# variator_380V_v2_0.net
KiCad netlist of a schematic drawn in EAGLE
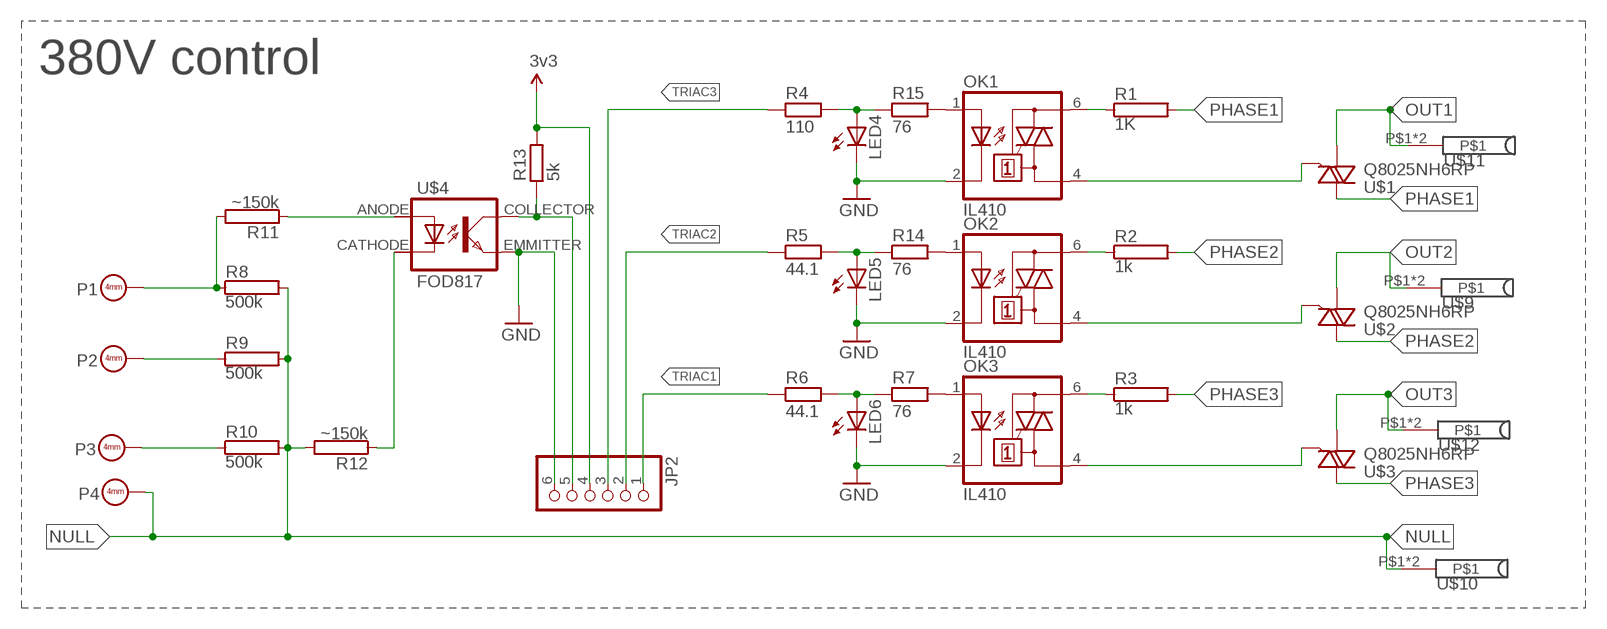
[diagram p0: schematic, sheet 1]

(export (version "E")
  (design (tool "Eeschema 10.0.6"))
  (components
    (comp (ref "JP2")
      (value "PINHD-1X6/90")
      (footprint "eagle-import:1X06_90")
      (libsource (lib "eagle-import") (part "PINHD-1X6/90"))
    )
    (comp (ref "LED4")
      (value "LED5MM")
      (footprint "eagle-import:LED5MM")
      (libsource (lib "eagle-import") (part "LED5MM"))
    )
    (comp (ref "LED5")
      (value "LED5MM")
      (footprint "eagle-import:LED5MM")
      (libsource (lib "eagle-import") (part "LED5MM"))
    )
    (comp (ref "LED6")
      (value "LED5MM")
      (footprint "eagle-import:LED5MM")
      (libsource (lib "eagle-import") (part "LED5MM"))
    )
    (comp (ref "OK1")
      (value "IL410")
      (footprint "eagle-import:DIL06")
      (fields (field (name "MF") "VISHAY/TELEFUNKEN"))
      (libsource (lib "eagle-import") (part "IL410"))
    )
    (comp (ref "OK2")
      (value "IL410")
      (footprint "eagle-import:DIL06")
      (fields (field (name "MF") "VISHAY/TELEFUNKEN"))
      (libsource (lib "eagle-import") (part "IL410"))
    )
    (comp (ref "OK3")
      (value "IL410")
      (footprint "eagle-import:DIL06")
      (fields (field (name "MF") "VISHAY/TELEFUNKEN"))
      (libsource (lib "eagle-import") (part "IL410"))
    )
    (comp (ref "P1")
      (value "BANANA")
      (footprint "eagle-import:BANANA")
      (libsource (lib "eagle-import") (part "adi_v1.4_BANANA"))
    )
    (comp (ref "P2")
      (value "BANANA")
      (footprint "eagle-import:BANANA")
      (libsource (lib "eagle-import") (part "adi_v1.4_BANANA"))
    )
    (comp (ref "P3")
      (value "BANANA")
      (footprint "eagle-import:BANANA")
      (libsource (lib "eagle-import") (part "adi_v1.4_BANANA"))
    )
    (comp (ref "P4")
      (value "BANANA")
      (footprint "eagle-import:BANANA")
      (libsource (lib "eagle-import") (part "adi_v1.4_BANANA"))
    )
    (comp (ref "R1")
      (value "1K")
      (footprint "eagle-import:HPS58")
      (libsource (lib "eagle-import") (part "RHPS58"))
    )
    (comp (ref "R2")
      (value "1k")
      (footprint "eagle-import:HPS58")
      (libsource (lib "eagle-import") (part "RHPS58"))
    )
    (comp (ref "R3")
      (value "1k")
      (footprint "eagle-import:HPS58")
      (libsource (lib "eagle-import") (part "RHPS58"))
    )
    (comp (ref "R4")
      (value "110")
      (footprint "eagle-import:1206")
      (libsource (lib "eagle-import") (part "R1206"))
    )
    (comp (ref "R5")
      (value "44.1")
      (footprint "eagle-import:1206")
      (libsource (lib "eagle-import") (part "R1206"))
    )
    (comp (ref "R6")
      (value "44.1")
      (footprint "eagle-import:1206")
      (libsource (lib "eagle-import") (part "R1206"))
    )
    (comp (ref "R7")
      (value "76")
      (footprint "eagle-import:1206")
      (libsource (lib "eagle-import") (part "R1206"))
    )
    (comp (ref "R8")
      (value "500k")
      (footprint "eagle-import:HPS58")
      (libsource (lib "eagle-import") (part "RHPS58"))
    )
    (comp (ref "R9")
      (value "500k")
      (footprint "eagle-import:HPS58")
      (libsource (lib "eagle-import") (part "RHPS58"))
    )
    (comp (ref "R10")
      (value "500k")
      (footprint "eagle-import:HPS58")
      (libsource (lib "eagle-import") (part "RHPS58"))
    )
    (comp (ref "R11")
      (value "~150k")
      (footprint "eagle-import:HPS58")
      (libsource (lib "eagle-import") (part "RHPS58"))
    )
    (comp (ref "R12")
      (value "~150k")
      (footprint "eagle-import:HPS58")
      (libsource (lib "eagle-import") (part "RHPS58"))
    )
    (comp (ref "R13")
      (value "5k")
      (footprint "eagle-import:1206")
      (libsource (lib "eagle-import") (part "R1206"))
    )
    (comp (ref "R14")
      (value "76")
      (footprint "eagle-import:1206")
      (libsource (lib "eagle-import") (part "R1206"))
    )
    (comp (ref "R15")
      (value "76")
      (footprint "eagle-import:1206")
      (libsource (lib "eagle-import") (part "R1206"))
    )
    (comp (ref "U$1")
      (value "Q8025NH6RP")
      (footprint "eagle-import:TO-263")
      (libsource (lib "eagle-import") (part "Q8025NH6RP"))
    )
    (comp (ref "U$2")
      (value "Q8025NH6RP")
      (footprint "eagle-import:TO-263")
      (libsource (lib "eagle-import") (part "Q8025NH6RP"))
    )
    (comp (ref "U$3")
      (value "Q8025NH6RP")
      (footprint "eagle-import:TO-263")
      (libsource (lib "eagle-import") (part "Q8025NH6RP"))
    )
    (comp (ref "U$4")
      (value "FOD817")
      (footprint "eagle-import:FOD_4PIN")
      (libsource (lib "eagle-import") (part "FOD817"))
    )
    (comp (ref "U$9")
      (value "BANANA")
      (footprint "eagle-import:BANANA")
      (libsource (lib "eagle-import") (part "BANANA"))
    )
    (comp (ref "U$10")
      (value "BANANA")
      (footprint "eagle-import:BANANA")
      (libsource (lib "eagle-import") (part "BANANA"))
    )
    (comp (ref "U$11")
      (value "BANANA")
      (footprint "eagle-import:BANANA")
      (libsource (lib "eagle-import") (part "BANANA"))
    )
    (comp (ref "U$12")
      (value "BANANA")
      (footprint "eagle-import:BANANA")
      (libsource (lib "eagle-import") (part "BANANA"))
    )
  )
  (nets
    (net (code "1") (name "3v3") (class "Default")
      (node (ref "JP2") (pin "4") (pinfunction "4_4") (pintype "passive"))
      (node (ref "R13") (pin "2") (pinfunction "2_2") (pintype "passive"))
    )
    (net (code "2") (name "GND") (class "Default")
      (node (ref "JP2") (pin "6") (pinfunction "6_6") (pintype "passive"))
      (node (ref "LED4") (pin "K") (pinfunction "C_K") (pintype "passive"))
      (node (ref "LED5") (pin "K") (pinfunction "C_K") (pintype "passive"))
      (node (ref "LED6") (pin "K") (pinfunction "C_K") (pintype "passive"))
      (node (ref "OK1") (pin "2") (pinfunction "C_2") (pintype "passive"))
      (node (ref "OK2") (pin "2") (pinfunction "C_2") (pintype "passive"))
      (node (ref "OK3") (pin "2") (pinfunction "C_2") (pintype "passive"))
      (node (ref "U$4") (pin "EMMITTER") (pinfunction "EMIT_EMMITTER") (pintype "passive"))
    )
    (net (code "3") (name "NULL") (class "Default")
      (node (ref "P4") (pin "P$1") (pinfunction "1_P$1") (pintype "passive"))
      (node (ref "R10") (pin "2") (pinfunction "2_2") (pintype "passive"))
      (node (ref "R12") (pin "2") (pinfunction "2_2") (pintype "passive"))
      (node (ref "R8") (pin "2") (pinfunction "2_2") (pintype "passive"))
      (node (ref "R9") (pin "2") (pinfunction "2_2") (pintype "passive"))
      (node (ref "U$10") (pin "P$1") (pinfunction "P$1_P$1") (pintype "bidirectional"))
      (node (ref "U$10") (pin "P$2") (pinfunction "P$1_P$2") (pintype "bidirectional"))
    )
    (net (code "4") (name "Net-(LED4-PadA)") (class "Default")
      (node (ref "LED4") (pin "A") (pinfunction "A_A") (pintype "passive"))
      (node (ref "R15") (pin "1") (pinfunction "1_1") (pintype "passive"))
      (node (ref "R4") (pin "2") (pinfunction "2_2") (pintype "passive"))
    )
    (net (code "5") (name "Net-(LED5-PadA)") (class "Default")
      (node (ref "LED5") (pin "A") (pinfunction "A_A") (pintype "passive"))
      (node (ref "R14") (pin "1") (pinfunction "1_1") (pintype "passive"))
      (node (ref "R5") (pin "2") (pinfunction "2_2") (pintype "passive"))
    )
    (net (code "6") (name "Net-(LED6-PadA)") (class "Default")
      (node (ref "LED6") (pin "A") (pinfunction "A_A") (pintype "passive"))
      (node (ref "R6") (pin "2") (pinfunction "2_2") (pintype "passive"))
      (node (ref "R7") (pin "1") (pinfunction "1_1") (pintype "passive"))
    )
    (net (code "7") (name "Net-(OK1-A)") (class "Default")
      (node (ref "OK1") (pin "1") (pinfunction "A_1") (pintype "passive"))
      (node (ref "R15") (pin "2") (pinfunction "2_2") (pintype "passive"))
    )
    (net (code "8") (name "Net-(OK1-A1)") (class "Default")
      (node (ref "OK1") (pin "4") (pinfunction "A1_4") (pintype "passive"))
      (node (ref "U$1") (pin "G") (pinfunction "G_G") (pintype "passive"))
    )
    (net (code "9") (name "Net-(OK1-A2)") (class "Default")
      (node (ref "OK1") (pin "6") (pinfunction "A2_6") (pintype "passive"))
      (node (ref "R1") (pin "1") (pinfunction "1_1") (pintype "passive"))
    )
    (net (code "10") (name "Net-(OK2-A)") (class "Default")
      (node (ref "OK2") (pin "1") (pinfunction "A_1") (pintype "passive"))
      (node (ref "R14") (pin "2") (pinfunction "2_2") (pintype "passive"))
    )
    (net (code "11") (name "Net-(OK2-A1)") (class "Default")
      (node (ref "OK2") (pin "4") (pinfunction "A1_4") (pintype "passive"))
      (node (ref "U$2") (pin "G") (pinfunction "G_G") (pintype "passive"))
    )
    (net (code "12") (name "Net-(OK2-A2)") (class "Default")
      (node (ref "OK2") (pin "6") (pinfunction "A2_6") (pintype "passive"))
      (node (ref "R2") (pin "1") (pinfunction "1_1") (pintype "passive"))
    )
    (net (code "13") (name "Net-(OK3-A)") (class "Default")
      (node (ref "OK3") (pin "1") (pinfunction "A_1") (pintype "passive"))
      (node (ref "R7") (pin "2") (pinfunction "2_2") (pintype "passive"))
    )
    (net (code "14") (name "Net-(OK3-A1)") (class "Default")
      (node (ref "OK3") (pin "4") (pinfunction "A1_4") (pintype "passive"))
      (node (ref "U$3") (pin "G") (pinfunction "G_G") (pintype "passive"))
    )
    (net (code "15") (name "Net-(OK3-A2)") (class "Default")
      (node (ref "OK3") (pin "6") (pinfunction "A2_6") (pintype "passive"))
      (node (ref "R3") (pin "1") (pinfunction "1_1") (pintype "passive"))
    )
    (net (code "16") (name "Net-(R11-Pad1)") (class "Default")
      (node (ref "R11") (pin "1") (pinfunction "1_1") (pintype "passive"))
      (node (ref "U$4") (pin "ANODE") (pinfunction "ANODE_ANODE") (pintype "passive"))
    )
    (net (code "17") (name "Net-(R12-Pad1)") (class "Default")
      (node (ref "R12") (pin "1") (pinfunction "1_1") (pintype "passive"))
      (node (ref "U$4") (pin "CATHODE") (pinfunction "CATHODE_CATHODE") (pintype "passive"))
    )
    (net (code "18") (name "Net-(U$4-COL)") (class "Default")
      (node (ref "JP2") (pin "5") (pinfunction "5_5") (pintype "passive"))
      (node (ref "R13") (pin "1") (pinfunction "1_1") (pintype "passive"))
      (node (ref "U$4") (pin "COLLECTOR") (pinfunction "COL_COLLECTOR") (pintype "passive"))
    )
    (net (code "19") (name "OUT1") (class "Default")
      (node (ref "U$1") (pin "T1") (pinfunction "T1_T1") (pintype "passive"))
      (node (ref "U$11") (pin "P$1") (pinfunction "P$1_P$1") (pintype "bidirectional"))
      (node (ref "U$11") (pin "P$2") (pinfunction "P$1_P$2") (pintype "bidirectional"))
    )
    (net (code "20") (name "OUT2") (class "Default")
      (node (ref "U$2") (pin "T1") (pinfunction "T1_T1") (pintype "passive"))
      (node (ref "U$9") (pin "P$1") (pinfunction "P$1_P$1") (pintype "bidirectional"))
      (node (ref "U$9") (pin "P$2") (pinfunction "P$1_P$2") (pintype "bidirectional"))
    )
    (net (code "21") (name "OUT3") (class "Default")
      (node (ref "U$12") (pin "P$1") (pinfunction "P$1_P$1") (pintype "bidirectional"))
      (node (ref "U$12") (pin "P$2") (pinfunction "P$1_P$2") (pintype "bidirectional"))
      (node (ref "U$3") (pin "T1") (pinfunction "T1_T1") (pintype "passive"))
    )
    (net (code "22") (name "PHASE1") (class "Default")
      (node (ref "P1") (pin "P$1") (pinfunction "1_P$1") (pintype "passive"))
      (node (ref "R1") (pin "2") (pinfunction "2_2") (pintype "passive"))
      (node (ref "R11") (pin "2") (pinfunction "2_2") (pintype "passive"))
      (node (ref "R8") (pin "1") (pinfunction "1_1") (pintype "passive"))
      (node (ref "U$1") (pin "T2") (pinfunction "T2_T2") (pintype "passive"))
    )
    (net (code "23") (name "PHASE2") (class "Default")
      (node (ref "P2") (pin "P$1") (pinfunction "1_P$1") (pintype "passive"))
      (node (ref "R2") (pin "2") (pinfunction "2_2") (pintype "passive"))
      (node (ref "R9") (pin "1") (pinfunction "1_1") (pintype "passive"))
      (node (ref "U$2") (pin "T2") (pinfunction "T2_T2") (pintype "passive"))
    )
    (net (code "24") (name "PHASE3") (class "Default")
      (node (ref "P3") (pin "P$1") (pinfunction "1_P$1") (pintype "passive"))
      (node (ref "R10") (pin "1") (pinfunction "1_1") (pintype "passive"))
      (node (ref "R3") (pin "2") (pinfunction "2_2") (pintype "passive"))
      (node (ref "U$3") (pin "T2") (pinfunction "T2_T2") (pintype "passive"))
    )
    (net (code "25") (name "TRIAC1") (class "Default")
      (node (ref "JP2") (pin "1") (pinfunction "1_1") (pintype "passive"))
      (node (ref "R6") (pin "1") (pinfunction "1_1") (pintype "passive"))
    )
    (net (code "26") (name "TRIAC2") (class "Default")
      (node (ref "JP2") (pin "2") (pinfunction "2_2") (pintype "passive"))
      (node (ref "R5") (pin "1") (pinfunction "1_1") (pintype "passive"))
    )
    (net (code "27") (name "TRIAC3") (class "Default")
      (node (ref "JP2") (pin "3") (pinfunction "3_3") (pintype "passive"))
      (node (ref "R4") (pin "1") (pinfunction "1_1") (pintype "passive"))
    )
  )
)
